# Sheet1.net
KiCad netlist of a schematic drawn in Altium Designer
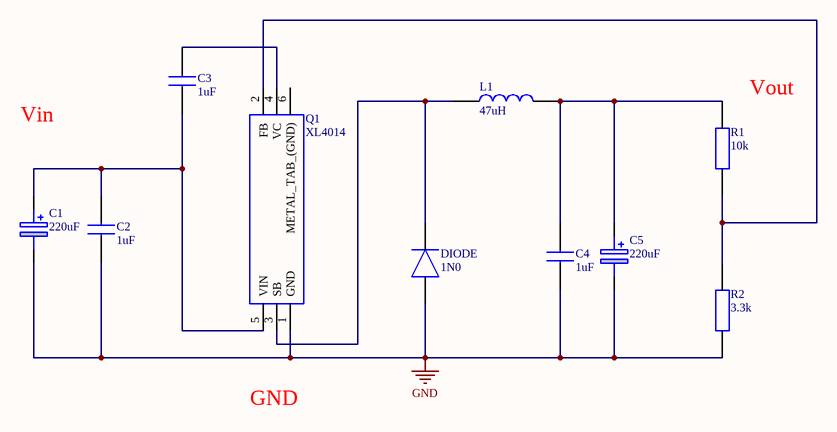
[diagram p0: Sheet1.SchDoc]

(export (version "E")
  (design (tool "Eeschema 10.0.6"))
  (components
    (comp (ref "C1")
      (value "220uF")
      (footprint "FKV(K16)")
      (fields
        (field (name "MANUFACTURER_PART_NUMBER") "EEVFK2A221M")
        (field (name "RS PART NUMBER") "5370679")
      )
      (libsource (lib "EEVFK2A221M") (part "EEVFK2A221M"))
    )
    (comp (ref "C2")
      (value "1uF")
      (footprint "CAPC2012X145N")
      (description "Multilayer Ceramic Capacitors MLCC - SMD/SMT 0805 0.1uF 50volts X7R 5%")
      (fields (field (name "MANUFACTURER_PART_NUMBER") "GRM21BR71H104JA01L"))
      (libsource (lib "GRM21BR71H104JA01L") (part "GRM21BR71H104JA01L"))
    )
    (comp (ref "C3")
      (value "1uF")
      (footprint "CAPC2012X145N")
      (description "Multilayer Ceramic Capacitors MLCC - SMD/SMT 0805 0.1uF 50volts X7R 5%")
      (fields (field (name "MANUFACTURER_PART_NUMBER") "GRM21BR71H104JA01L"))
      (libsource (lib "GRM21BR71H104JA01L") (part "GRM21BR71H104JA01L"))
    )
    (comp (ref "C4")
      (value "1uF")
      (footprint "CAPC2012X145N")
      (description "Multilayer Ceramic Capacitors MLCC - SMD/SMT 0805 0.1uF 50volts X7R 5%")
      (fields (field (name "MANUFACTURER_PART_NUMBER") "GRM21BR71H104JA01L"))
      (libsource (lib "GRM21BR71H104JA01L") (part "GRM21BR71H104JA01L"))
    )
    (comp (ref "C5")
      (value "220uF")
      (footprint "FKV(K16)")
      (fields
        (field (name "MANUFACTURER_PART_NUMBER") "EEVFK2A221M")
        (field (name "RS PART NUMBER") "5370679")
      )
      (libsource (lib "EEVFK2A221M") (part "EEVFK2A221M"))
    )
    (comp (ref "DIODE")
      (value "1N0")
      (footprint "DIOM5336X244N")
      (description "HY Electronic Corp SS54B, SMT Rectifier Schottky Diode, 40V 5A, 2-Pin SMB")
      (fields (field (name "MANUFACTURER_PART_NUMBER") "SS54B") (field (name "RS PART NUMBER") "1711461"))
      (libsource (lib "SS54B") (part "SS54B"))
    )
    (comp (ref "L1")
      (value "47uH")
      (footprint "INDPM110100X400N")
      (fields
        (field (name "MANUFACTURER_PART_NUMBER") "SRP1038A-470M")
        (field (name "RS PART NUMBER") "1728637")
      )
      (libsource (lib "SRP1038A-470M") (part "SRP1038A-470M"))
    )
    (comp (ref "Q1")
      (value "XL4014")
      (footprint "TO-263-5")
      (description "DC / DC converters in the housing TO263-5L, Voltage Regulator, Buck Converter, Switching Regulator")
      (fields (field (name "MANUFACTURER_PART_NUMBER") "AP1506-50K5G-13"))
      (libsource (lib "AP1506-50K5G-13") (part "AP1506-50K5G-13"))
    )
    (comp (ref "R1")
      (value "10k")
      (footprint "RESC2012X65N")
      (description "Thick Film Resistors - SMD 0805 510Kohm 1% High VoltageAEC-Q200")
      (fields (field (name "MANUFACTURER_PART_NUMBER") "KTR10EZPF5103"))
      (libsource (lib "10kOhm") (part "KTR10EZPF5103"))
    )
    (comp (ref "R2")
      (value "3.3k")
      (footprint "RESC2012X65N")
      (description "Thick Film Resistors - SMD 0805 510Kohm 1% High VoltageAEC-Q200")
      (fields (field (name "MANUFACTURER_PART_NUMBER") "KTR10EZPF5103"))
      (libsource (lib "10kOhm") (part "KTR10EZPF5103"))
    )
  )
  (nets
    (net (code "1") (name "GND") (class "Default")
      (node (ref "C1") (pin "2") (pinfunction "-_2") (pintype "passive"))
      (node (ref "C2") (pin "1") (pinfunction "1_1") (pintype "passive"))
      (node (ref "C4") (pin "1") (pinfunction "1_1") (pintype "passive"))
      (node (ref "C5") (pin "2") (pinfunction "-_2") (pintype "passive"))
      (node (ref "DIODE") (pin "2") (pinfunction "A_2") (pintype "passive"))
      (node (ref "Q1") (pin "1") (pinfunction "GND_1") (pintype "passive"))
      (node (ref "R2") (pin "1") (pinfunction "1_1") (pintype "passive"))
    )
    (net (code "2") (name "Net-(C1-+)") (class "Default")
      (node (ref "C1") (pin "1") (pinfunction "+_1") (pintype "passive"))
      (node (ref "C2") (pin "2") (pinfunction "2_2") (pintype "passive"))
      (node (ref "C3") (pin "1") (pinfunction "1_1") (pintype "passive"))
      (node (ref "Q1") (pin "5") (pinfunction "VIN_5") (pintype "passive"))
    )
    (net (code "3") (name "Net-(C5-+)") (class "Default")
      (node (ref "C4") (pin "2") (pinfunction "2_2") (pintype "passive"))
      (node (ref "C5") (pin "1") (pinfunction "+_1") (pintype "passive"))
      (node (ref "L1") (pin "2") (pinfunction "2_2") (pintype "passive"))
      (node (ref "R1") (pin "1") (pinfunction "1_1") (pintype "passive"))
    )
    (net (code "4") (name "Net-(DIODE-K)") (class "Default")
      (node (ref "DIODE") (pin "1") (pinfunction "K_1") (pintype "passive"))
      (node (ref "L1") (pin "1") (pinfunction "1_1") (pintype "passive"))
      (node (ref "Q1") (pin "3") (pinfunction "SB_3") (pintype "passive"))
    )
    (net (code "5") (name "Net-(Q1-FB)") (class "Default")
      (node (ref "Q1") (pin "2") (pinfunction "FB_2") (pintype "passive"))
      (node (ref "R1") (pin "2") (pinfunction "2_2") (pintype "passive"))
      (node (ref "R2") (pin "2") (pinfunction "2_2") (pintype "passive"))
    )
    (net (code "6") (name "Net-(Q1-VC)") (class "Default")
      (node (ref "C3") (pin "2") (pinfunction "2_2") (pintype "passive"))
      (node (ref "Q1") (pin "4") (pinfunction "VC_4") (pintype "passive"))
    )
    (net (code "7") (name "unconnected-(Q1-METAL_TAB_(GND)-Pad6)") (class "Default")
      (node (ref "Q1") (pin "6") (pinfunction "METAL_TAB_(GND)_6") (pintype "passive"))
    )
  )
)
